# DM2080_SPARE_IMX378.net
KiCad netlist of a schematic drawn in Altium Designer
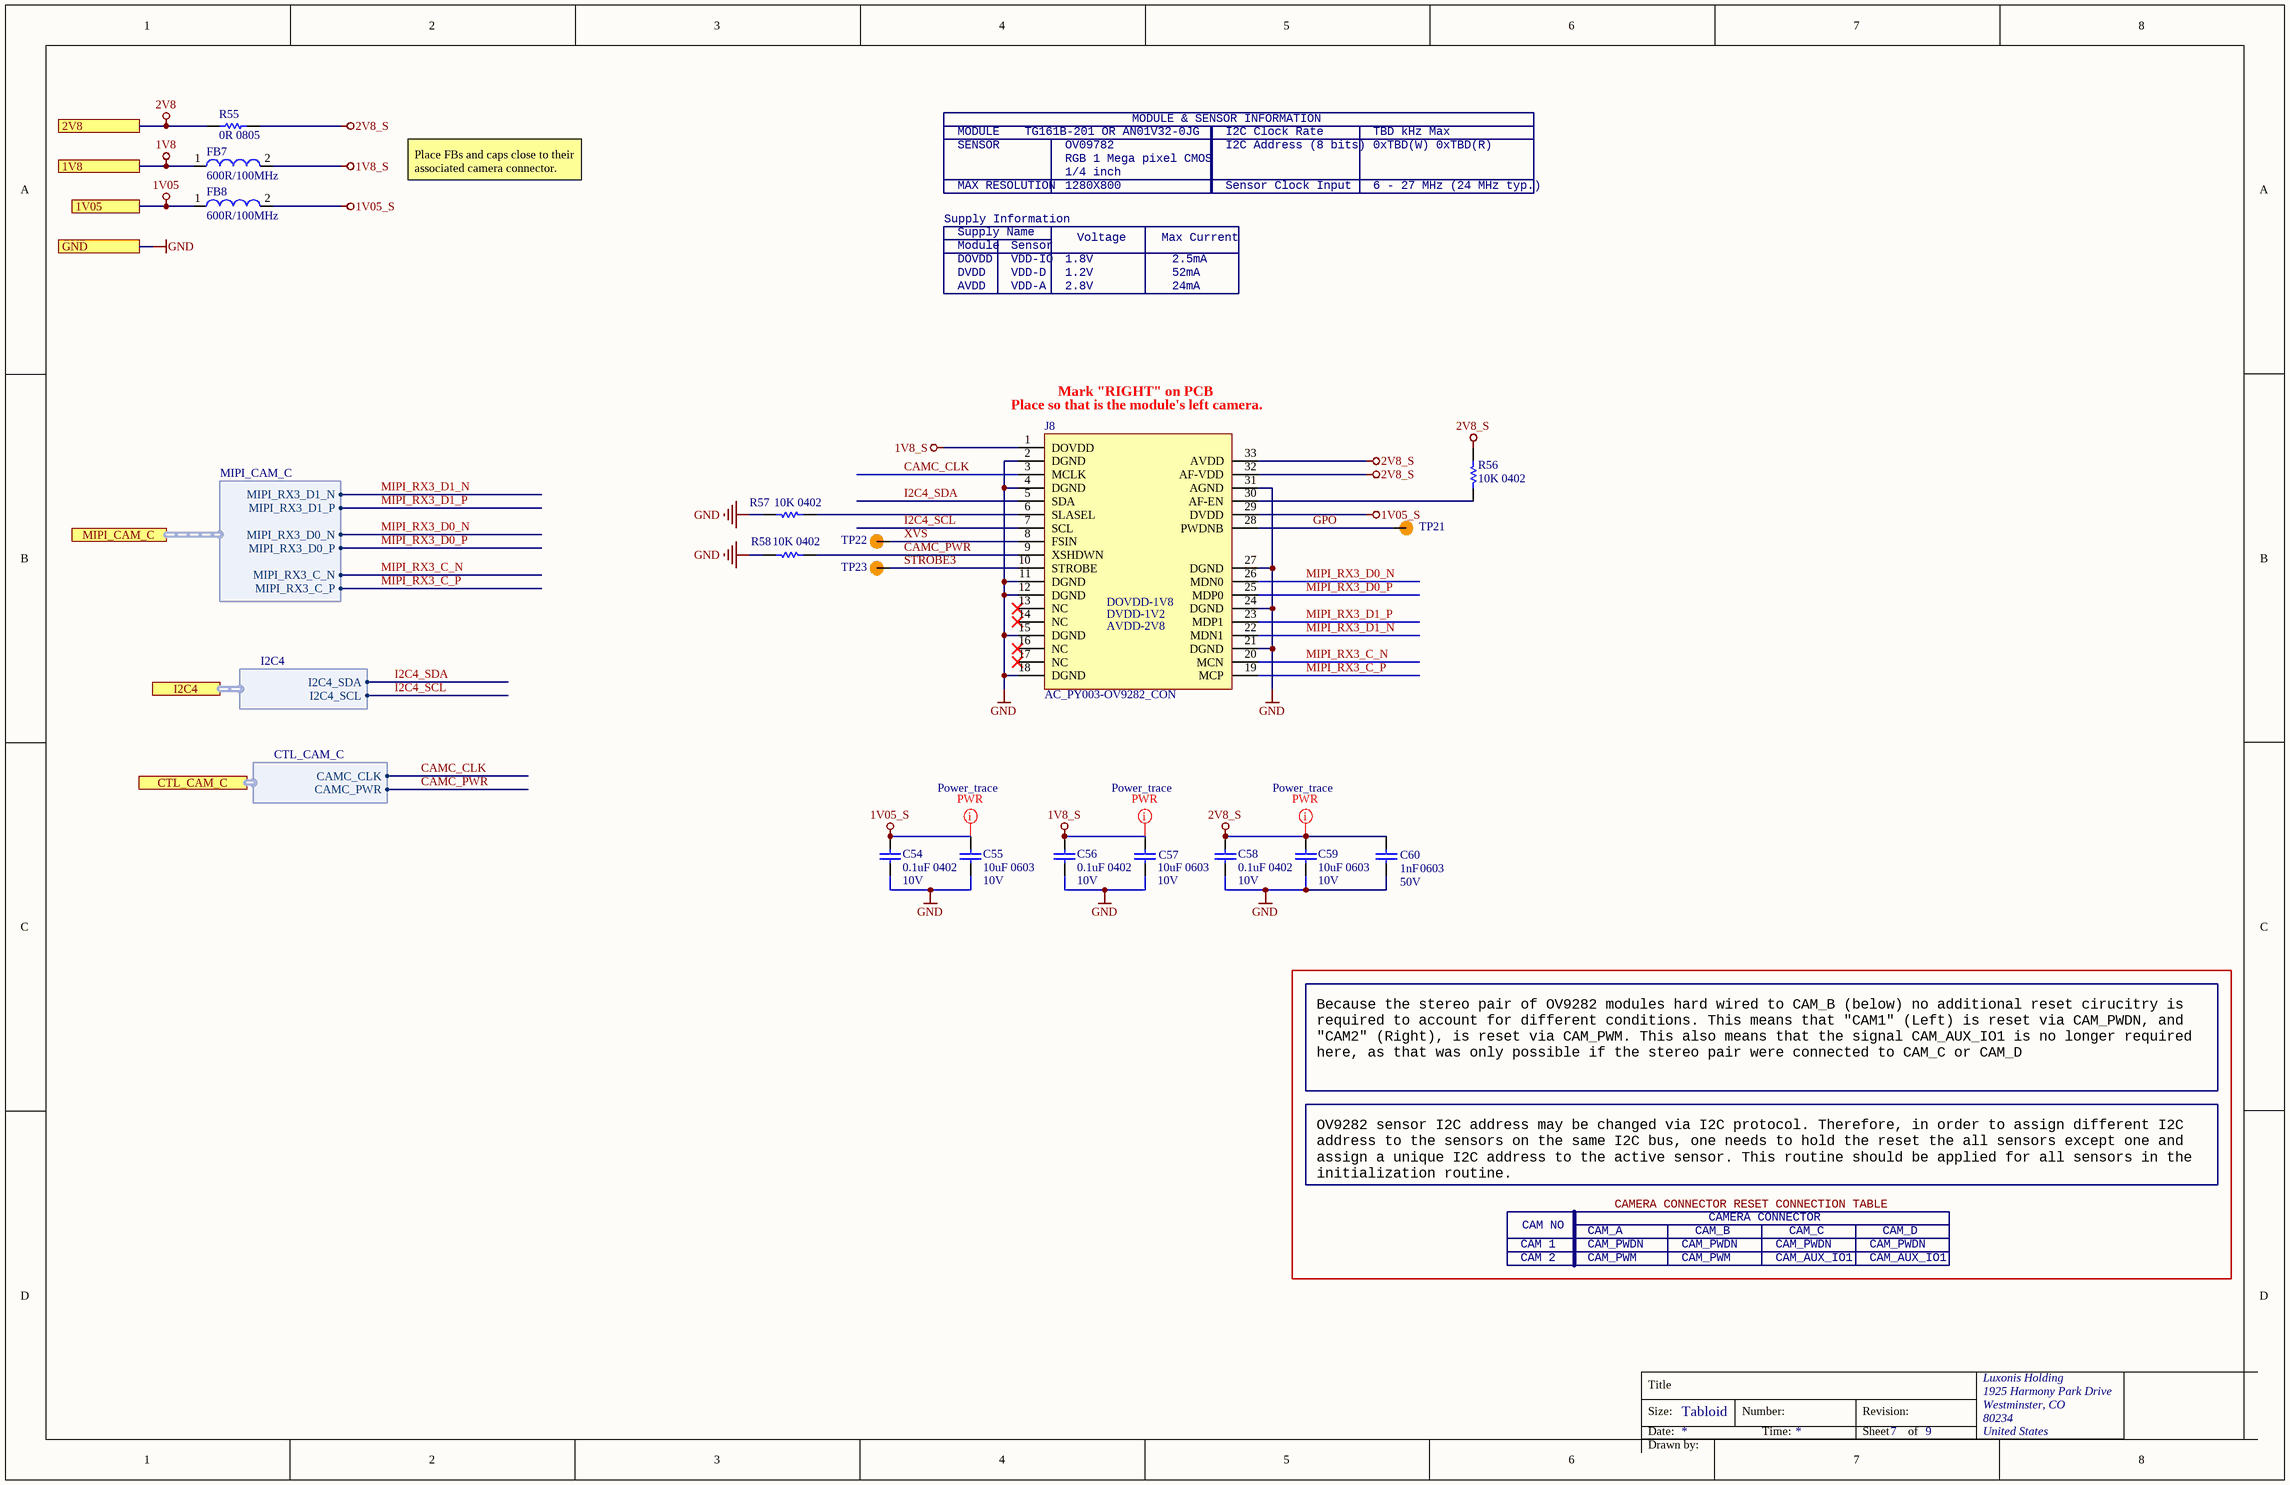
[diagram p0: DM2080_SPARE_IMX378.SchDoc]

(export (version "E")
  (design (tool "Eeschema 10.0.6"))
  (components
    (comp (ref "C54")
      (value "0.1uF 0402")
      (footprint "CAP_Altium_Vault_Generic:CAPC0402(1005)70_L")
      (description "CAP CER 0.1UF 10V X7R 0402 5%")
      (fields (field (name "TOLERANCE") "5%") (field (name "VOLTAGE RATING") "10V"))
      (libsource (lib "LuxonisMaster") (part "GRM155R71A104JA01D"))
    )
    (comp (ref "C55")
      (value "10uF 0603")
      (footprint "CAP_Altium_Vault_Generic:CAPC0603(1608)100_L")
      (description "CAP CER 10UF 10V X5R 0603 20%")
      (fields (field (name "TOLERANCE") "20%") (field (name "VOLTAGE RATING") "10V"))
      (libsource (lib "LuxonisMaster") (part "GRM188R61A106ME69D"))
    )
    (comp (ref "C56")
      (value "0.1uF 0402")
      (footprint "CAP_Altium_Vault_Generic:CAPC0402(1005)70_L")
      (description "CAP CER 0.1UF 10V X7R 0402 5%")
      (fields (field (name "TOLERANCE") "5%") (field (name "VOLTAGE RATING") "10V"))
      (libsource (lib "LuxonisMaster") (part "GRM155R71A104JA01D"))
    )
    (comp (ref "C57")
      (value "10uF 0603")
      (footprint "CAP_Altium_Vault_Generic:CAPC0603(1608)100_L")
      (description "CAP CER 10UF 10V X5R 0603 20%")
      (fields (field (name "TOLERANCE") "20%") (field (name "VOLTAGE RATING") "10V"))
      (libsource (lib "LuxonisMaster") (part "GRM188R61A106ME69D"))
    )
    (comp (ref "C58")
      (value "0.1uF 0402")
      (footprint "CAP_Altium_Vault_Generic:CAPC0402(1005)70_L")
      (description "CAP CER 0.1UF 10V X7R 0402 5%")
      (fields (field (name "TOLERANCE") "5%") (field (name "VOLTAGE RATING") "10V"))
      (libsource (lib "LuxonisMaster") (part "GRM155R71A104JA01D"))
    )
    (comp (ref "C59")
      (value "10uF 0603")
      (footprint "CAP_Altium_Vault_Generic:CAPC0603(1608)100_L")
      (description "CAP CER 10UF 10V X5R 0603 20%")
      (fields (field (name "TOLERANCE") "20%") (field (name "VOLTAGE RATING") "10V"))
      (libsource (lib "LuxonisMaster") (part "GRM188R61A106ME69D"))
    )
    (comp (ref "C60")
      (value "1nF 0603 C0G")
      (footprint "CAP_Altium_Vault_Generic:CAPC0603(1608)100_L")
      (description "CAP CER 1000PF 50V C0G/NP0 0603")
      (fields
        (field (name "MANUFACTURER") "Murata")
        (field (name "MANUFACTURER PART NUMBER") "GRM1885C1H102FA01D")
        (field (name "CASE/PACKAGE") "0603")
        (field (name "CAPACITANCE") "1nF")
        (field (name "VOLTAGE RATING") "50V")
      )
      (libsource (lib "LuxonisMaster") (part "GRM1885C1H102FA01D"))
    )
    (comp (ref "FB7")
      (value "600R/100MHz")
      (footprint "LuxonisMaster:2508056017Y2")
      (description "FERRITE BEAD, 0.1OHM, 2A, 0805, 600R/100MHz")
      (fields (field (name "TOLERANCE") "25%"))
      (libsource (lib "LuxonisMaster") (part "2508056017Y2"))
    )
    (comp (ref "FB8")
      (value "600R/100MHz")
      (footprint "LuxonisMaster:2508056017Y2")
      (description "FERRITE BEAD, 0.1OHM, 2A, 0805, 600R/100MHz")
      (fields (field (name "TOLERANCE") "25%"))
      (libsource (lib "LuxonisMaster") (part "2508056017Y2"))
    )
    (comp (ref "J8")
      (value "AC_PY003-OV9282_CON")
      (footprint "AC-PY003-OV9282")
      (description "FFC/FPC Connector, 33 Contact(s), 1 Row(s), Female, Right Angle, Surface Mount Terminal")
      (libsource (lib "Luxonis LLC") (part "AC_PY003-OV9282_CON"))
    )
    (comp (ref "R55")
      (value "0R 0805")
      (footprint "RESC0805(2012)_L")
      (description "RES SMD 0.0R OHM 1% 1/8W 0805")
      (libsource (lib "LuxonisMaster") (part "CRCW08050000Z0EA"))
    )
    (comp (ref "R56")
      (value "10K 0402")
      (footprint "RES_Altium_Vault_Generic:RESC0402(1005)_L")
      (fields (field (name "TOLERANCE") "1%"))
      (libsource (lib "LuxonisMaster") (part "RC0402FR-1310KL"))
    )
    (comp (ref "R57")
      (value "10K 0402")
      (footprint "RES_Altium_Vault_Generic:RESC0402(1005)_L")
      (fields (field (name "TOLERANCE") "1%"))
      (libsource (lib "LuxonisMaster") (part "RC0402FR-1310KL"))
    )
    (comp (ref "R58")
      (value "10K 0402")
      (footprint "RES_Altium_Vault_Generic:RESC0402(1005)_L")
      (fields (field (name "TOLERANCE") "1%"))
      (libsource (lib "LuxonisMaster") (part "RC0402FR-1310KL"))
    )
    (comp (ref "TP21")
      (value "TP100_200_NS")
      (footprint "LuxonisMaster:TP100_200_NS")
      (libsource (lib "LuxonisMaster") (part "TEST_POINT"))
    )
    (comp (ref "TP22")
      (value "TP100_200_NS")
      (footprint "LuxonisMaster:TP100_200_NS")
      (libsource (lib "LuxonisMaster") (part "TEST_POINT"))
    )
    (comp (ref "TP23")
      (value "TP100_200_NS")
      (footprint "LuxonisMaster:TP100_200_NS")
      (libsource (lib "LuxonisMaster") (part "TEST_POINT"))
    )
  )
  (nets
    (net (code "4") (name "/CAMC_CLK") (class "Default")
      (node (ref "J8") (pin "3") (pinfunction "MCLK_3") (pintype "passive"))
    )
    (net (code "5") (name "/CAMC_PWR") (class "Default")
      (node (ref "J8") (pin "9") (pinfunction "XSHDWN_9") (pintype "passive"))
      (node (ref "R58") (pin "1") (pinfunction "1_1") (pintype "passive"))
    )
    (net (code "6") (name "/GPO") (class "Default")
      (node (ref "J8") (pin "28") (pinfunction "PWDNB_28") (pintype "passive"))
      (node (ref "TP21") (pin "1") (pintype "passive"))
    )
    (net (code "7") (name "/I2C4_SCL") (class "Default")
      (node (ref "J8") (pin "7") (pinfunction "SCL_7") (pintype "passive"))
    )
    (net (code "8") (name "/I2C4_SDA") (class "Default")
      (node (ref "J8") (pin "5") (pinfunction "SDA_5") (pintype "passive"))
    )
    (net (code "9") (name "/MIPI_RX3_C_N") (class "Default")
      (node (ref "J8") (pin "20") (pinfunction "MCN_20") (pintype "passive"))
    )
    (net (code "10") (name "/MIPI_RX3_C_P") (class "Default")
      (node (ref "J8") (pin "19") (pinfunction "MCP_19") (pintype "passive"))
    )
    (net (code "11") (name "/MIPI_RX3_D0_N") (class "Default")
      (node (ref "J8") (pin "26") (pinfunction "MDN0_26") (pintype "passive"))
    )
    (net (code "12") (name "/MIPI_RX3_D0_P") (class "Default")
      (node (ref "J8") (pin "25") (pinfunction "MDP0_25") (pintype "passive"))
    )
    (net (code "13") (name "/MIPI_RX3_D1_N") (class "Default")
      (node (ref "J8") (pin "22") (pinfunction "MDN1_22") (pintype "passive"))
    )
    (net (code "14") (name "/MIPI_RX3_D1_P") (class "Default")
      (node (ref "J8") (pin "23") (pinfunction "MDP1_23") (pintype "passive"))
    )
    (net (code "15") (name "/STROBE3") (class "Default")
      (node (ref "J8") (pin "10") (pinfunction "STROBE_10") (pintype "passive"))
      (node (ref "TP23") (pin "1") (pintype "passive"))
    )
    (net (code "16") (name "/XVS") (class "Default")
      (node (ref "J8") (pin "8") (pinfunction "FSIN_8") (pintype "passive"))
      (node (ref "TP22") (pin "1") (pintype "passive"))
    )
    (net (code "20") (name "1V05") (class "Default")
      (node (ref "FB8") (pin "1") (pinfunction "1_1") (pintype "passive"))
    )
    (net (code "21") (name "1V05_S") (class "Default")
      (node (ref "C54") (pin "2") (pinfunction "2_2") (pintype "passive"))
      (node (ref "C55") (pin "2") (pinfunction "2_2") (pintype "passive"))
      (node (ref "FB8") (pin "2") (pinfunction "2_2") (pintype "passive"))
      (node (ref "J8") (pin "29") (pinfunction "DVDD_29") (pintype "passive"))
    )
    (net (code "22") (name "1V8") (class "Default")
      (node (ref "FB7") (pin "1") (pinfunction "1_1") (pintype "passive"))
    )
    (net (code "23") (name "1V8_S") (class "Default")
      (node (ref "C56") (pin "2") (pinfunction "2_2") (pintype "passive"))
      (node (ref "C57") (pin "2") (pinfunction "2_2") (pintype "passive"))
      (node (ref "FB7") (pin "2") (pinfunction "2_2") (pintype "passive"))
      (node (ref "J8") (pin "1") (pinfunction "DOVDD_1") (pintype "passive"))
    )
    (net (code "24") (name "2V8") (class "Default")
      (node (ref "R55") (pin "1") (pinfunction "1_1") (pintype "passive"))
    )
    (net (code "25") (name "2V8_S") (class "Default")
      (node (ref "C58") (pin "2") (pinfunction "2_2") (pintype "passive"))
      (node (ref "C59") (pin "2") (pinfunction "2_2") (pintype "passive"))
      (node (ref "C60") (pin "2") (pinfunction "2_2") (pintype "passive"))
      (node (ref "J8") (pin "32") (pinfunction "AF-VDD_32") (pintype "passive"))
      (node (ref "J8") (pin "33") (pinfunction "AVDD_33") (pintype "passive"))
      (node (ref "R55") (pin "2") (pinfunction "2_2") (pintype "passive"))
      (node (ref "R56") (pin "1") (pinfunction "1_1") (pintype "passive"))
    )
    (net (code "26") (name "GND") (class "Default")
      (node (ref "C54") (pin "1") (pinfunction "1_1") (pintype "passive"))
      (node (ref "C55") (pin "1") (pinfunction "1_1") (pintype "passive"))
      (node (ref "C56") (pin "1") (pinfunction "1_1") (pintype "passive"))
      (node (ref "C57") (pin "1") (pinfunction "1_1") (pintype "passive"))
      (node (ref "C58") (pin "1") (pinfunction "1_1") (pintype "passive"))
      (node (ref "C59") (pin "1") (pinfunction "1_1") (pintype "passive"))
      (node (ref "C60") (pin "1") (pinfunction "1_1") (pintype "passive"))
      (node (ref "J8") (pin "11") (pinfunction "DGND_11") (pintype "passive"))
      (node (ref "J8") (pin "12") (pinfunction "DGND_12") (pintype "passive"))
      (node (ref "J8") (pin "15") (pinfunction "DGND_15") (pintype "passive"))
      (node (ref "J8") (pin "18") (pinfunction "DGND_18") (pintype "passive"))
      (node (ref "J8") (pin "2") (pinfunction "DGND_2") (pintype "passive"))
      (node (ref "J8") (pin "21") (pinfunction "DGND_21") (pintype "passive"))
      (node (ref "J8") (pin "24") (pinfunction "DGND_24") (pintype "passive"))
      (node (ref "J8") (pin "27") (pinfunction "DGND_27") (pintype "passive"))
      (node (ref "J8") (pin "31") (pinfunction "AGND_31") (pintype "passive"))
      (node (ref "J8") (pin "4") (pinfunction "DGND_4") (pintype "passive"))
      (node (ref "R57") (pin "2") (pinfunction "2_2") (pintype "passive"))
      (node (ref "R58") (pin "2") (pinfunction "2_2") (pintype "passive"))
    )
    (net (code "27") (name "Net-(J8-AF-EN)") (class "Default")
      (node (ref "J8") (pin "30") (pinfunction "AF-EN_30") (pintype "passive"))
      (node (ref "R56") (pin "2") (pinfunction "2_2") (pintype "passive"))
    )
    (net (code "28") (name "Net-(J8-SLASEL)") (class "Default")
      (node (ref "J8") (pin "6") (pinfunction "SLASEL_6") (pintype "passive"))
      (node (ref "R57") (pin "1") (pinfunction "1_1") (pintype "passive"))
    )
    (net (code "29") (name "unconnected-(J8-NC-Pad13)") (class "Default")
      (node (ref "J8") (pin "13") (pinfunction "NC_13") (pintype "passive+no_connect"))
    )
    (net (code "30") (name "unconnected-(J8-NC-Pad14)") (class "Default")
      (node (ref "J8") (pin "14") (pinfunction "NC_14") (pintype "passive+no_connect"))
    )
    (net (code "31") (name "unconnected-(J8-NC-Pad16)") (class "Default")
      (node (ref "J8") (pin "16") (pinfunction "NC_16") (pintype "passive+no_connect"))
    )
    (net (code "32") (name "unconnected-(J8-NC-Pad17)") (class "Default")
      (node (ref "J8") (pin "17") (pinfunction "NC_17") (pintype "passive+no_connect"))
    )
  )
)
